# stepUp.net
KiCad netlist of a schematic drawn in EAGLE
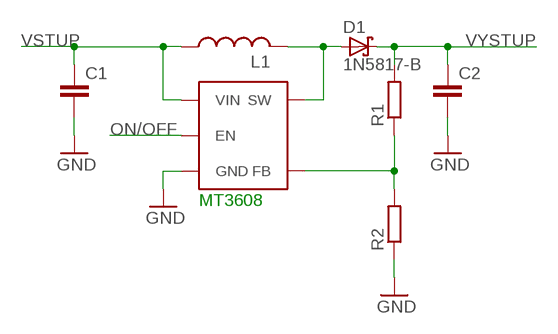
[diagram p0: schematic, sheet 1]

(export (version "E")
  (design (tool "Eeschema 10.0.6"))
  (components
    (comp (ref "C1")
      (value "C5/3.5")
      (footprint "eagle-import:C5B3.5")
      (libsource (lib "eagle-import") (part "C5/3.5"))
    )
    (comp (ref "C2")
      (value "C5/3.5")
      (footprint "eagle-import:C5B3.5")
      (libsource (lib "eagle-import") (part "C5/3.5"))
    )
    (comp (ref "D1")
      (value "1N5817-B")
      (footprint "eagle-import:DO41-7.6")
      (libsource (lib "eagle-import") (part "1N5817-B"))
    )
    (comp (ref "L1")
      (value "L-US0204/5")
      (footprint "eagle-import:0204_5")
      (libsource (lib "eagle-import") (part "L-US0204/5"))
    )
    (comp (ref "MT3608")
      (value "MT3605")
      (footprint "eagle-import:MT3608")
      (libsource (lib "eagle-import") (part "MT3605"))
    )
    (comp (ref "R1") (value "R") (footprint "eagle-import:R0805") (libsource (lib "eagle-import") (part "R")))
    (comp (ref "R2") (value "R") (footprint "eagle-import:R0805") (libsource (lib "eagle-import") (part "R")))
  )
  (nets
    (net (code "1") (name "/ON{slash}OFF") (class "Default")
      (node (ref "MT3608") (pin "P$1") (pinfunction "EN_P$1") (pintype "bidirectional"))
    )
    (net (code "2") (name "/VSTUP") (class "Default")
      (node (ref "C1") (pin "1") (pinfunction "1_1") (pintype "passive"))
      (node (ref "L1") (pin "1") (pinfunction "1_1") (pintype "passive"))
      (node (ref "MT3608") (pin "P$5") (pinfunction "VIN_P$5") (pintype "bidirectional"))
    )
    (net (code "3") (name "/VYSTUP") (class "Default")
      (node (ref "C2") (pin "1") (pinfunction "1_1") (pintype "passive"))
      (node (ref "D1") (pin "C") (pinfunction "C_C") (pintype "passive"))
      (node (ref "R1") (pin "2") (pinfunction "2_2") (pintype "passive"))
    )
    (net (code "4") (name "GND") (class "Default")
      (node (ref "C1") (pin "2") (pinfunction "2_2") (pintype "passive"))
      (node (ref "C2") (pin "2") (pinfunction "2_2") (pintype "passive"))
      (node (ref "MT3608") (pin "P$3") (pinfunction "GND_P$3") (pintype "bidirectional"))
      (node (ref "R2") (pin "1") (pinfunction "1_1") (pintype "passive"))
    )
    (net (code "5") (name "Net-(MT3608-FB)") (class "Default")
      (node (ref "MT3608") (pin "P$2") (pinfunction "FB_P$2") (pintype "bidirectional"))
      (node (ref "R1") (pin "1") (pinfunction "1_1") (pintype "passive"))
      (node (ref "R2") (pin "2") (pinfunction "2_2") (pintype "passive"))
    )
    (net (code "6") (name "Net-(MT3608-SW)") (class "Default")
      (node (ref "D1") (pin "A") (pinfunction "A_A") (pintype "passive"))
      (node (ref "L1") (pin "2") (pinfunction "2_2") (pintype "passive"))
      (node (ref "MT3608") (pin "P$4") (pinfunction "SW_P$4") (pintype "bidirectional"))
    )
  )
)
